# TempProbe.net
KiCad netlist of a schematic drawn in EAGLE
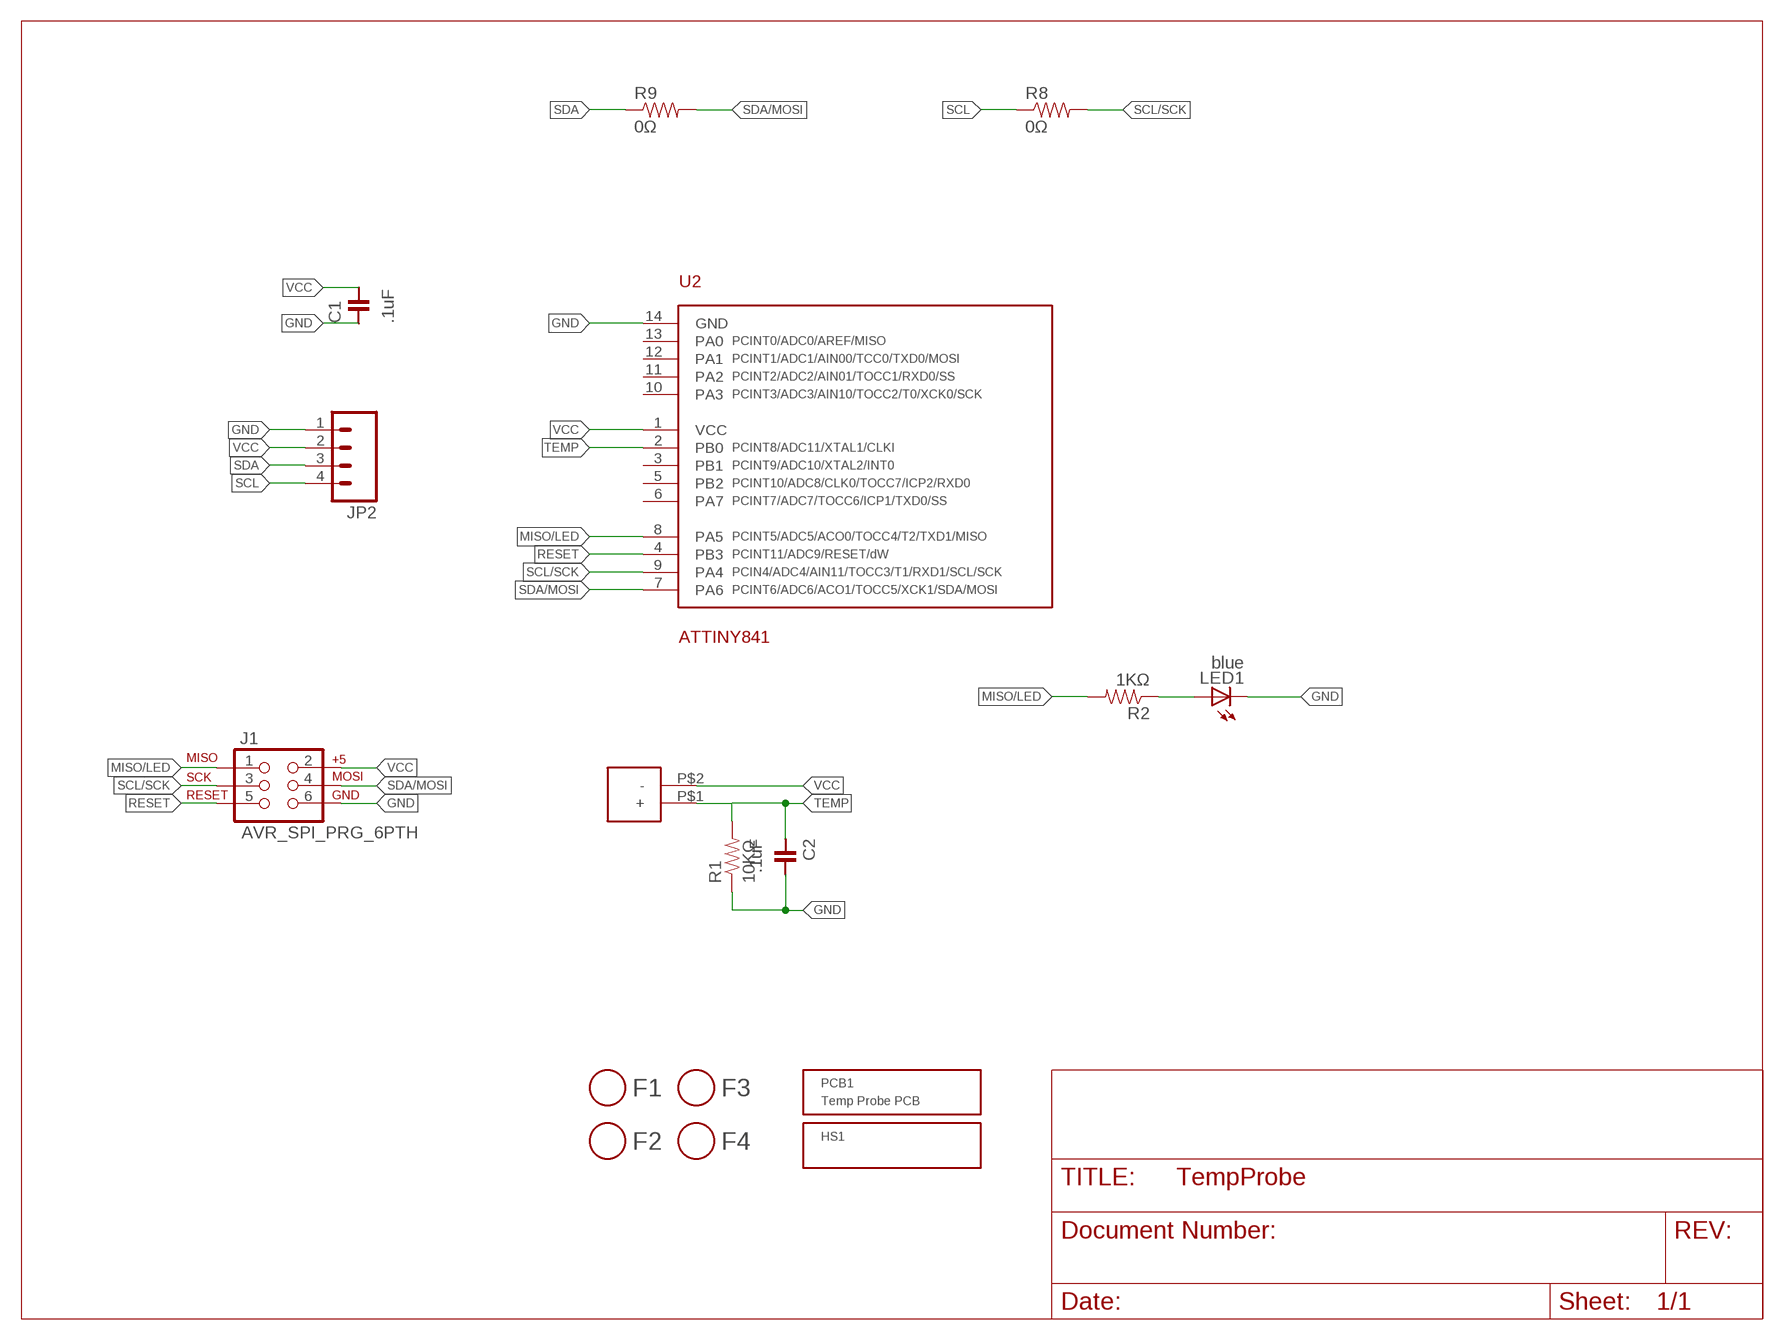
[diagram p0: schematic, sheet 1]

(export (version "E")
  (design (tool "Eeschema 10.0.6"))
  (components
    (comp (ref "C1")
      (value ".1uF")
      (footprint "eagle-import:0603")
      (fields (field (name "PARTNUM") "C0603C104K5RACTU"))
      (libsource (lib "eagle-import") (part "CAPACITOR-.1UF"))
    )
    (comp (ref "C2")
      (value ".1uF")
      (footprint "eagle-import:0603")
      (fields (field (name "PARTNUM") "C0603C104K5RACTU"))
      (libsource (lib "eagle-import") (part "CAPACITOR-.1UF"))
    )
    (comp (ref "F1")
      (value "FIDUCIAL")
      (footprint "eagle-import:FIDUCIAL_1MM")
      (libsource (lib "eagle-import") (part "FIDUCIAL"))
    )
    (comp (ref "F2")
      (value "FIDUCIAL")
      (footprint "eagle-import:FIDUCIAL_1MM")
      (libsource (lib "eagle-import") (part "FIDUCIAL"))
    )
    (comp (ref "F3")
      (value "FIDUCIAL")
      (footprint "eagle-import:FIDUCIAL_1MM")
      (libsource (lib "eagle-import") (part "FIDUCIAL"))
    )
    (comp (ref "F4")
      (value "FIDUCIAL")
      (footprint "eagle-import:FIDUCIAL_1MM")
      (libsource (lib "eagle-import") (part "FIDUCIAL"))
    )
    (comp (ref "J1")
      (value "AVR_SPI_PRG_6PTH")
      (footprint "eagle-import:2X3")
      (libsource (lib "eagle-import") (part "AVR_SPI_PRG_6PTH"))
    )
    (comp (ref "JP2")
      (value "M041X04_NO_SILK")
      (footprint "eagle-import:1X04_NO_SILK")
      (libsource (lib "eagle-import") (part "M041X04_NO_SILK"))
    )
    (comp (ref "LED1")
      (value "blue")
      (footprint "eagle-import:0805-LED")
      (fields (field (name "PARTNUM") "LTST-C171TBKT"))
      (libsource (lib "eagle-import") (part "LED-0805-BLUE"))
    )
    (comp (ref "PROBE1")
      (value "TEMP-PROBE")
      (footprint "eagle-import:TEMP_PROBE")
      (fields (field (name "PARTNUM") "NTCLE413E2103F102L"))
      (libsource (lib "eagle-import") (part "TEMP-PROBE"))
    )
    (comp (ref "R1")
      (value "10KΩ")
      (footprint "eagle-import:0603")
      (fields (field (name "PARTNUM") "ERJ-3EKF1002V"))
      (libsource (lib "eagle-import") (part "RESISTOR-10KΩ"))
    )
    (comp (ref "R2")
      (value "1KΩ")
      (footprint "eagle-import:0603")
      (fields (field (name "PARTNUM") "ERJ-3EKF1001V"))
      (libsource (lib "eagle-import") (part "RESISTOR-1KΩ"))
    )
    (comp (ref "R8")
      (value "0Ω")
      (footprint "eagle-import:0603")
      (fields (field (name "PARTNUM") "ERJ-3GEY0R00V"))
      (libsource (lib "eagle-import") (part "RESISTOR-0Ω"))
    )
    (comp (ref "R9")
      (value "0Ω")
      (footprint "eagle-import:0603")
      (fields (field (name "PARTNUM") "ERJ-3GEY0R00V"))
      (libsource (lib "eagle-import") (part "RESISTOR-0Ω"))
    )
    (comp (ref "U2")
      (value "ATTINY841")
      (footprint "eagle-import:SOIC-14")
      (fields (field (name "PARTNUM") "ATTINY841-SSUR"))
      (libsource (lib "eagle-import") (part "ATTINY841"))
    )
  )
  (nets
    (net (code "1") (name "GND") (class "Default")
      (node (ref "C1") (pin "2") (pinfunction "2_2") (pintype "passive"))
      (node (ref "C2") (pin "1") (pinfunction "1_1") (pintype "passive"))
      (node (ref "J1") (pin "6") (pinfunction "6_6") (pintype "passive"))
      (node (ref "JP2") (pin "1") (pinfunction "1_1") (pintype "passive"))
      (node (ref "LED1") (pin "C") (pinfunction "C_C") (pintype "passive"))
      (node (ref "R1") (pin "1") (pinfunction "1_1") (pintype "passive"))
      (node (ref "U2") (pin "14") (pinfunction "GND_14") (pintype "bidirectional"))
    )
    (net (code "2") (name "MISO{slash}LED") (class "Default")
      (node (ref "J1") (pin "1") (pinfunction "1_1") (pintype "passive"))
      (node (ref "R2") (pin "2") (pinfunction "2_2") (pintype "passive"))
      (node (ref "U2") (pin "8") (pinfunction "PA5_8") (pintype "bidirectional"))
    )
    (net (code "3") (name "Net-(LED1-PadA)") (class "Default")
      (node (ref "LED1") (pin "A") (pinfunction "A_A") (pintype "passive"))
      (node (ref "R2") (pin "1") (pinfunction "1_1") (pintype "passive"))
    )
    (net (code "4") (name "RESET") (class "Default")
      (node (ref "J1") (pin "5") (pinfunction "5_5") (pintype "passive"))
      (node (ref "U2") (pin "4") (pinfunction "PB3_4") (pintype "bidirectional"))
    )
    (net (code "5") (name "SCL") (class "Default")
      (node (ref "JP2") (pin "4") (pinfunction "4_4") (pintype "passive"))
      (node (ref "R8") (pin "1") (pinfunction "1_1") (pintype "passive"))
    )
    (net (code "6") (name "SCL{slash}SCK") (class "Default")
      (node (ref "J1") (pin "3") (pinfunction "3_3") (pintype "passive"))
      (node (ref "R8") (pin "2") (pinfunction "2_2") (pintype "passive"))
      (node (ref "U2") (pin "9") (pinfunction "PA4_9") (pintype "bidirectional"))
    )
    (net (code "7") (name "SDA") (class "Default")
      (node (ref "JP2") (pin "3") (pinfunction "3_3") (pintype "passive"))
      (node (ref "R9") (pin "1") (pinfunction "1_1") (pintype "passive"))
    )
    (net (code "8") (name "SDA{slash}MOSI") (class "Default")
      (node (ref "J1") (pin "4") (pinfunction "4_4") (pintype "passive"))
      (node (ref "R9") (pin "2") (pinfunction "2_2") (pintype "passive"))
      (node (ref "U2") (pin "7") (pinfunction "PA6_7") (pintype "bidirectional"))
    )
    (net (code "9") (name "TEMP") (class "Default")
      (node (ref "C2") (pin "2") (pinfunction "2_2") (pintype "passive"))
      (node (ref "PROBE1") (pin "P$1") (pinfunction "+_P$1") (pintype "bidirectional"))
      (node (ref "R1") (pin "2") (pinfunction "2_2") (pintype "passive"))
      (node (ref "U2") (pin "2") (pinfunction "PB0_2") (pintype "bidirectional"))
    )
    (net (code "10") (name "VCC") (class "Default")
      (node (ref "C1") (pin "1") (pinfunction "1_1") (pintype "passive"))
      (node (ref "J1") (pin "2") (pinfunction "2_2") (pintype "passive"))
      (node (ref "JP2") (pin "2") (pinfunction "2_2") (pintype "passive"))
      (node (ref "PROBE1") (pin "P$2") (pinfunction "-_P$2") (pintype "bidirectional"))
      (node (ref "U2") (pin "1") (pinfunction "VCC_1") (pintype "bidirectional"))
    )
    (net (code "11") (name "unconnected-(U2-PA0-Pad13)") (class "Default")
      (node (ref "U2") (pin "13") (pinfunction "PA0_13") (pintype "bidirectional"))
    )
    (net (code "12") (name "unconnected-(U2-PA1-Pad12)") (class "Default")
      (node (ref "U2") (pin "12") (pinfunction "PA1_12") (pintype "bidirectional"))
    )
    (net (code "13") (name "unconnected-(U2-PA2-Pad11)") (class "Default")
      (node (ref "U2") (pin "11") (pinfunction "PA2_11") (pintype "bidirectional"))
    )
    (net (code "14") (name "unconnected-(U2-PA3-Pad10)") (class "Default")
      (node (ref "U2") (pin "10") (pinfunction "PA3_10") (pintype "bidirectional"))
    )
    (net (code "15") (name "unconnected-(U2-PA7-Pad6)") (class "Default")
      (node (ref "U2") (pin "6") (pinfunction "PA7_6") (pintype "bidirectional"))
    )
    (net (code "16") (name "unconnected-(U2-PB1-Pad3)") (class "Default")
      (node (ref "U2") (pin "3") (pinfunction "PB1_3") (pintype "bidirectional"))
    )
    (net (code "17") (name "unconnected-(U2-PB2-Pad5)") (class "Default")
      (node (ref "U2") (pin "5") (pinfunction "PB2_5") (pintype "bidirectional"))
    )
  )
)
